# esp_prog.net
KiCad netlist of a schematic drawn in EAGLE
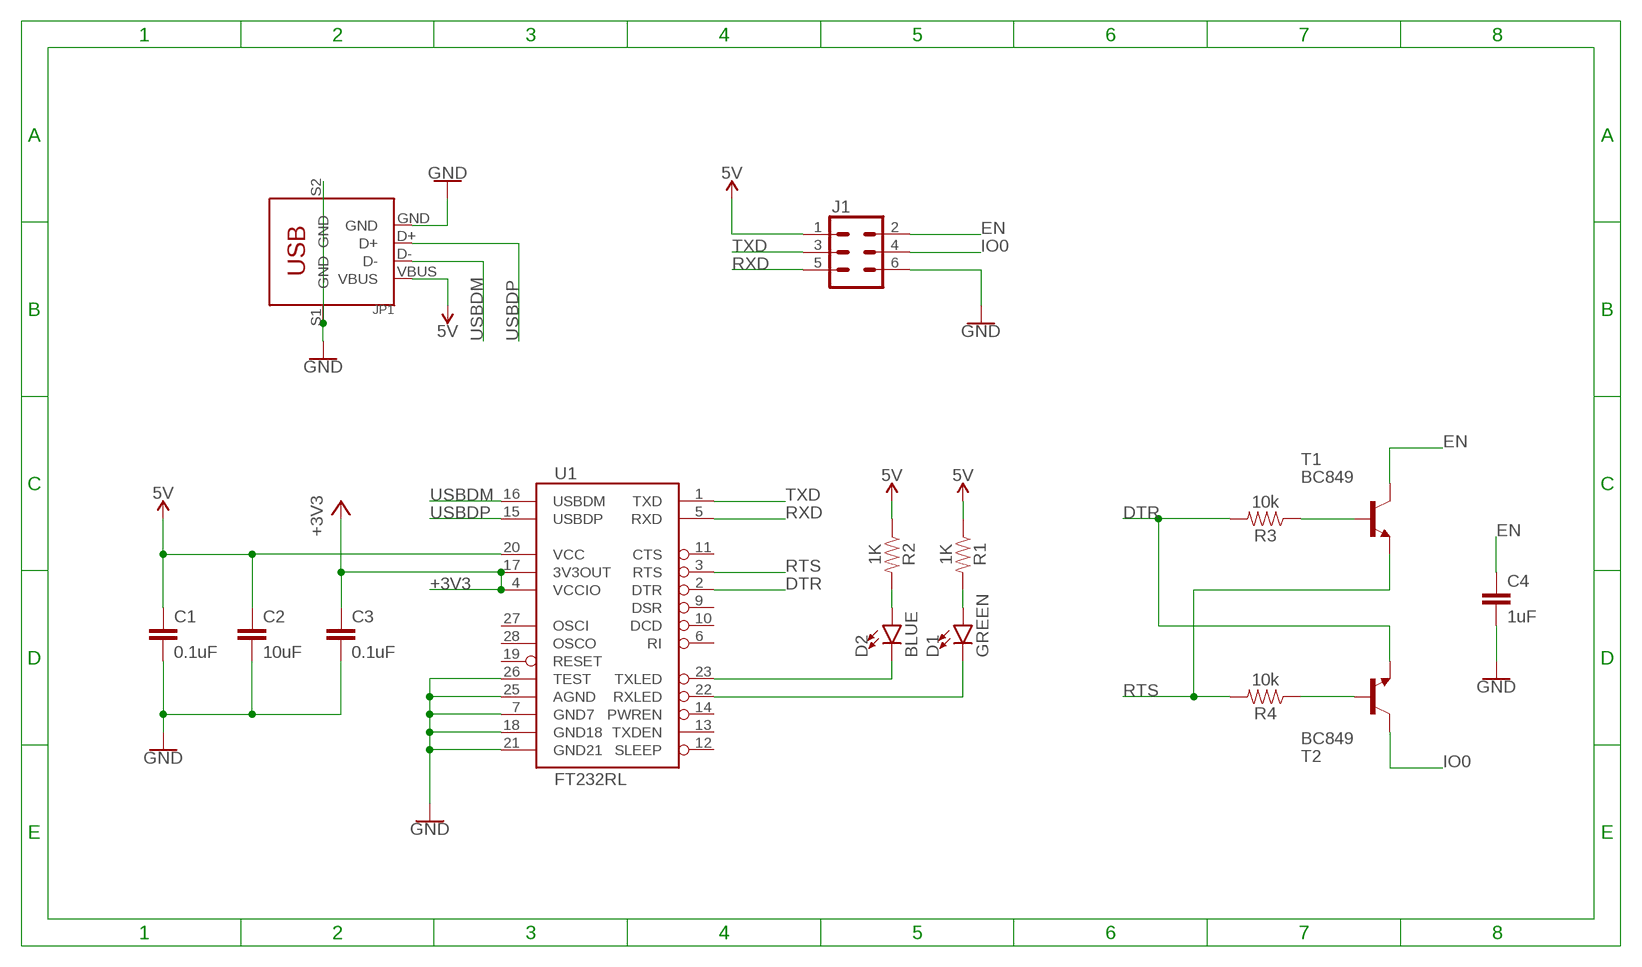
[diagram p0: schematic, sheet 1]

(export (version "E")
  (design (tool "Eeschema 10.0.6"))
  (components
    (comp (ref "C1")
      (value "0.1uF")
      (footprint "eagle-import:0603")
      (libsource (lib "eagle-import") (part "0.1UF-0603-25V-(+80/-20%)"))
    )
    (comp (ref "C2")
      (value "10uF")
      (footprint "eagle-import:0603")
      (libsource (lib "eagle-import") (part "10UF-0603-6.3V-20%"))
    )
    (comp (ref "C3")
      (value "0.1uF")
      (footprint "eagle-import:0603")
      (libsource (lib "eagle-import") (part "0.1UF-0603-25V-(+80/-20%)"))
    )
    (comp (ref "C4")
      (value "1uF")
      (footprint "eagle-import:0603")
      (libsource (lib "eagle-import") (part "10UF-0603-6.3V-20%"))
    )
    (comp (ref "D1")
      (value "GREEN")
      (footprint "eagle-import:LED-0603")
      (libsource (lib "eagle-import") (part "LED-GREEN0603"))
    )
    (comp (ref "D2")
      (value "BLUE")
      (footprint "eagle-import:LED-0603")
      (libsource (lib "eagle-import") (part "LED-BLUE0603"))
    )
    (comp (ref "J1")
      (value "CONN_03X2SHROUD")
      (footprint "eagle-import:2X3-SHROUDED")
      (libsource (lib "eagle-import") (part "CONN_03X2SHROUD"))
    )
    (comp (ref "JP1")
      (value "DIP-USB-B-TYPE-FMAL(4+2P-2.0-90D)")
      (footprint "eagle-import:USB4+2-2.5-90D-15.8X12MM")
      (libsource (lib "eagle-import") (part "DIP-USB-B-TYPE-FMAL(4+2P-2.0-90D)"))
    )
    (comp (ref "R1")
      (value "1K")
      (footprint "eagle-import:0603")
      (libsource (lib "eagle-import") (part "RESISTOR0603"))
    )
    (comp (ref "R2")
      (value "1K")
      (footprint "eagle-import:0603")
      (libsource (lib "eagle-import") (part "RESISTOR0603"))
    )
    (comp (ref "R3")
      (value "10k")
      (footprint "eagle-import:0603")
      (libsource (lib "eagle-import") (part "RESISTOR0603"))
    )
    (comp (ref "R4")
      (value "10k")
      (footprint "eagle-import:0603")
      (libsource (lib "eagle-import") (part "RESISTOR0603"))
    )
    (comp (ref "T1")
      (value "BC849")
      (footprint "eagle-import:SOT23")
      (libsource (lib "eagle-import") (part "BC849"))
    )
    (comp (ref "T2")
      (value "BC849")
      (footprint "eagle-import:SOT23")
      (libsource (lib "eagle-import") (part "BC849"))
    )
    (comp (ref "U1")
      (value "FT232RL")
      (footprint "eagle-import:SSOP28DB")
      (libsource (lib "eagle-import") (part "FT232RLSSOP"))
    )
  )
  (nets
    (net (code "1") (name "+3V3") (class "Default")
      (node (ref "C3") (pin "1") (pinfunction "1_1") (pintype "passive"))
      (node (ref "U1") (pin "17") (pinfunction "3V3OUT_17") (pintype "output"))
      (node (ref "U1") (pin "4") (pinfunction "VCCIO_4") (pintype "power_in"))
    )
    (net (code "2") (name "/DTR") (class "Default")
      (node (ref "R3") (pin "2") (pinfunction "2_2") (pintype "passive"))
      (node (ref "T2") (pin "2") (pinfunction "E_2") (pintype "passive"))
      (node (ref "U1") (pin "2") (pinfunction "DTR_2") (pintype "output"))
    )
    (net (code "3") (name "/EN") (class "Default")
      (node (ref "C4") (pin "1") (pinfunction "1_1") (pintype "passive"))
      (node (ref "J1") (pin "2") (pinfunction "2_2") (pintype "bidirectional"))
      (node (ref "T1") (pin "3") (pinfunction "C_3") (pintype "passive"))
    )
    (net (code "4") (name "/IO0") (class "Default")
      (node (ref "J1") (pin "4") (pinfunction "4_4") (pintype "bidirectional"))
      (node (ref "T2") (pin "3") (pinfunction "C_3") (pintype "passive"))
    )
    (net (code "5") (name "/RTS") (class "Default")
      (node (ref "R4") (pin "2") (pinfunction "2_2") (pintype "passive"))
      (node (ref "T1") (pin "2") (pinfunction "E_2") (pintype "passive"))
      (node (ref "U1") (pin "3") (pinfunction "RTS_3") (pintype "output"))
    )
    (net (code "6") (name "/RXD") (class "Default")
      (node (ref "J1") (pin "5") (pinfunction "5_5") (pintype "bidirectional"))
      (node (ref "U1") (pin "5") (pinfunction "RXD_5") (pintype "input"))
    )
    (net (code "7") (name "/TXD") (class "Default")
      (node (ref "J1") (pin "3") (pinfunction "3_3") (pintype "bidirectional"))
      (node (ref "U1") (pin "1") (pinfunction "TXD_1") (pintype "output"))
    )
    (net (code "8") (name "/USBDM") (class "Default")
      (node (ref "JP1") (pin "D-") (pinfunction "D-_D-") (pintype "bidirectional"))
      (node (ref "U1") (pin "16") (pinfunction "USBDM_16") (pintype "bidirectional"))
    )
    (net (code "9") (name "/USBDP") (class "Default")
      (node (ref "JP1") (pin "D+") (pinfunction "D+_D+") (pintype "bidirectional"))
      (node (ref "U1") (pin "15") (pinfunction "USBDP_15") (pintype "bidirectional"))
    )
    (net (code "10") (name "5V") (class "Default")
      (node (ref "C1") (pin "1") (pinfunction "1_1") (pintype "passive"))
      (node (ref "C2") (pin "1") (pinfunction "1_1") (pintype "passive"))
      (node (ref "J1") (pin "1") (pinfunction "1_1") (pintype "bidirectional"))
      (node (ref "JP1") (pin "VBUS") (pinfunction "VBUS_VBUS") (pintype "bidirectional"))
      (node (ref "R1") (pin "1") (pinfunction "1_1") (pintype "passive"))
      (node (ref "R2") (pin "1") (pinfunction "1_1") (pintype "passive"))
      (node (ref "U1") (pin "20") (pinfunction "VCC_20") (pintype "power_in"))
    )
    (net (code "11") (name "GND") (class "Default")
      (node (ref "C1") (pin "2") (pinfunction "2_2") (pintype "passive"))
      (node (ref "C2") (pin "2") (pinfunction "2_2") (pintype "passive"))
      (node (ref "C3") (pin "2") (pinfunction "2_2") (pintype "passive"))
      (node (ref "C4") (pin "2") (pinfunction "2_2") (pintype "passive"))
      (node (ref "J1") (pin "6") (pinfunction "6_6") (pintype "bidirectional"))
      (node (ref "JP1") (pin "GND") (pinfunction "GND_GND") (pintype "bidirectional"))
      (node (ref "JP1") (pin "S1") (pinfunction "GND_S1") (pintype "bidirectional"))
      (node (ref "JP1") (pin "S2") (pinfunction "GND_S2") (pintype "bidirectional"))
      (node (ref "U1") (pin "18") (pinfunction "GND18_18") (pintype "power_in"))
      (node (ref "U1") (pin "21") (pinfunction "GND21_21") (pintype "power_in"))
      (node (ref "U1") (pin "25") (pinfunction "AGND_25") (pintype "power_in"))
      (node (ref "U1") (pin "26") (pinfunction "TEST_26") (pintype "input"))
      (node (ref "U1") (pin "7") (pinfunction "GND7_7") (pintype "power_in"))
    )
    (net (code "12") (name "Net-(D1-PadA)") (class "Default")
      (node (ref "D1") (pin "A") (pinfunction "A_A") (pintype "passive"))
      (node (ref "R1") (pin "2") (pinfunction "2_2") (pintype "passive"))
    )
    (net (code "13") (name "Net-(D2-PadA)") (class "Default")
      (node (ref "D2") (pin "A") (pinfunction "A_A") (pintype "passive"))
      (node (ref "R2") (pin "2") (pinfunction "2_2") (pintype "passive"))
    )
    (net (code "14") (name "Net-(T1-B)") (class "Default")
      (node (ref "R3") (pin "1") (pinfunction "1_1") (pintype "passive"))
      (node (ref "T1") (pin "1") (pinfunction "B_1") (pintype "passive"))
    )
    (net (code "15") (name "Net-(T2-B)") (class "Default")
      (node (ref "R4") (pin "1") (pinfunction "1_1") (pintype "passive"))
      (node (ref "T2") (pin "1") (pinfunction "B_1") (pintype "passive"))
    )
    (net (code "16") (name "Net-(U1-RXLED)") (class "Default")
      (node (ref "D1") (pin "C") (pinfunction "C_C") (pintype "passive"))
      (node (ref "U1") (pin "22") (pinfunction "RXLED_22") (pintype "input"))
    )
    (net (code "17") (name "Net-(U1-TXLED)") (class "Default")
      (node (ref "D2") (pin "C") (pinfunction "C_C") (pintype "passive"))
      (node (ref "U1") (pin "23") (pinfunction "TXLED_23") (pintype "input"))
    )
    (net (code "18") (name "unconnected-(U1-CTS-Pad11)") (class "Default")
      (node (ref "U1") (pin "11") (pinfunction "CTS_11") (pintype "input"))
    )
    (net (code "19") (name "unconnected-(U1-DCD-Pad10)") (class "Default")
      (node (ref "U1") (pin "10") (pinfunction "DCD_10") (pintype "input"))
    )
    (net (code "20") (name "unconnected-(U1-DSR-Pad9)") (class "Default")
      (node (ref "U1") (pin "9") (pinfunction "DSR_9") (pintype "input"))
    )
    (net (code "21") (name "unconnected-(U1-OSCI-Pad27)") (class "Default")
      (node (ref "U1") (pin "27") (pinfunction "OSCI_27") (pintype "input"))
    )
    (net (code "22") (name "unconnected-(U1-OSCO-Pad28)") (class "Default")
      (node (ref "U1") (pin "28") (pinfunction "OSCO_28") (pintype "output"))
    )
    (net (code "23") (name "unconnected-(U1-PWREN-Pad14)") (class "Default")
      (node (ref "U1") (pin "14") (pinfunction "PWREN_14") (pintype "input"))
    )
    (net (code "24") (name "unconnected-(U1-RESET-Pad19)") (class "Default")
      (node (ref "U1") (pin "19") (pinfunction "RESET_19") (pintype "input"))
    )
    (net (code "25") (name "unconnected-(U1-RI-Pad6)") (class "Default")
      (node (ref "U1") (pin "6") (pinfunction "RI_6") (pintype "input"))
    )
    (net (code "26") (name "unconnected-(U1-SLEEP-Pad12)") (class "Default")
      (node (ref "U1") (pin "12") (pinfunction "SLEEP_12") (pintype "input"))
    )
    (net (code "27") (name "unconnected-(U1-TXDEN-Pad13)") (class "Default")
      (node (ref "U1") (pin "13") (pinfunction "TXDEN_13") (pintype "input"))
    )
  )
)
